# arpie_cv_tab.net
KiCad netlist of a schematic drawn in EAGLE
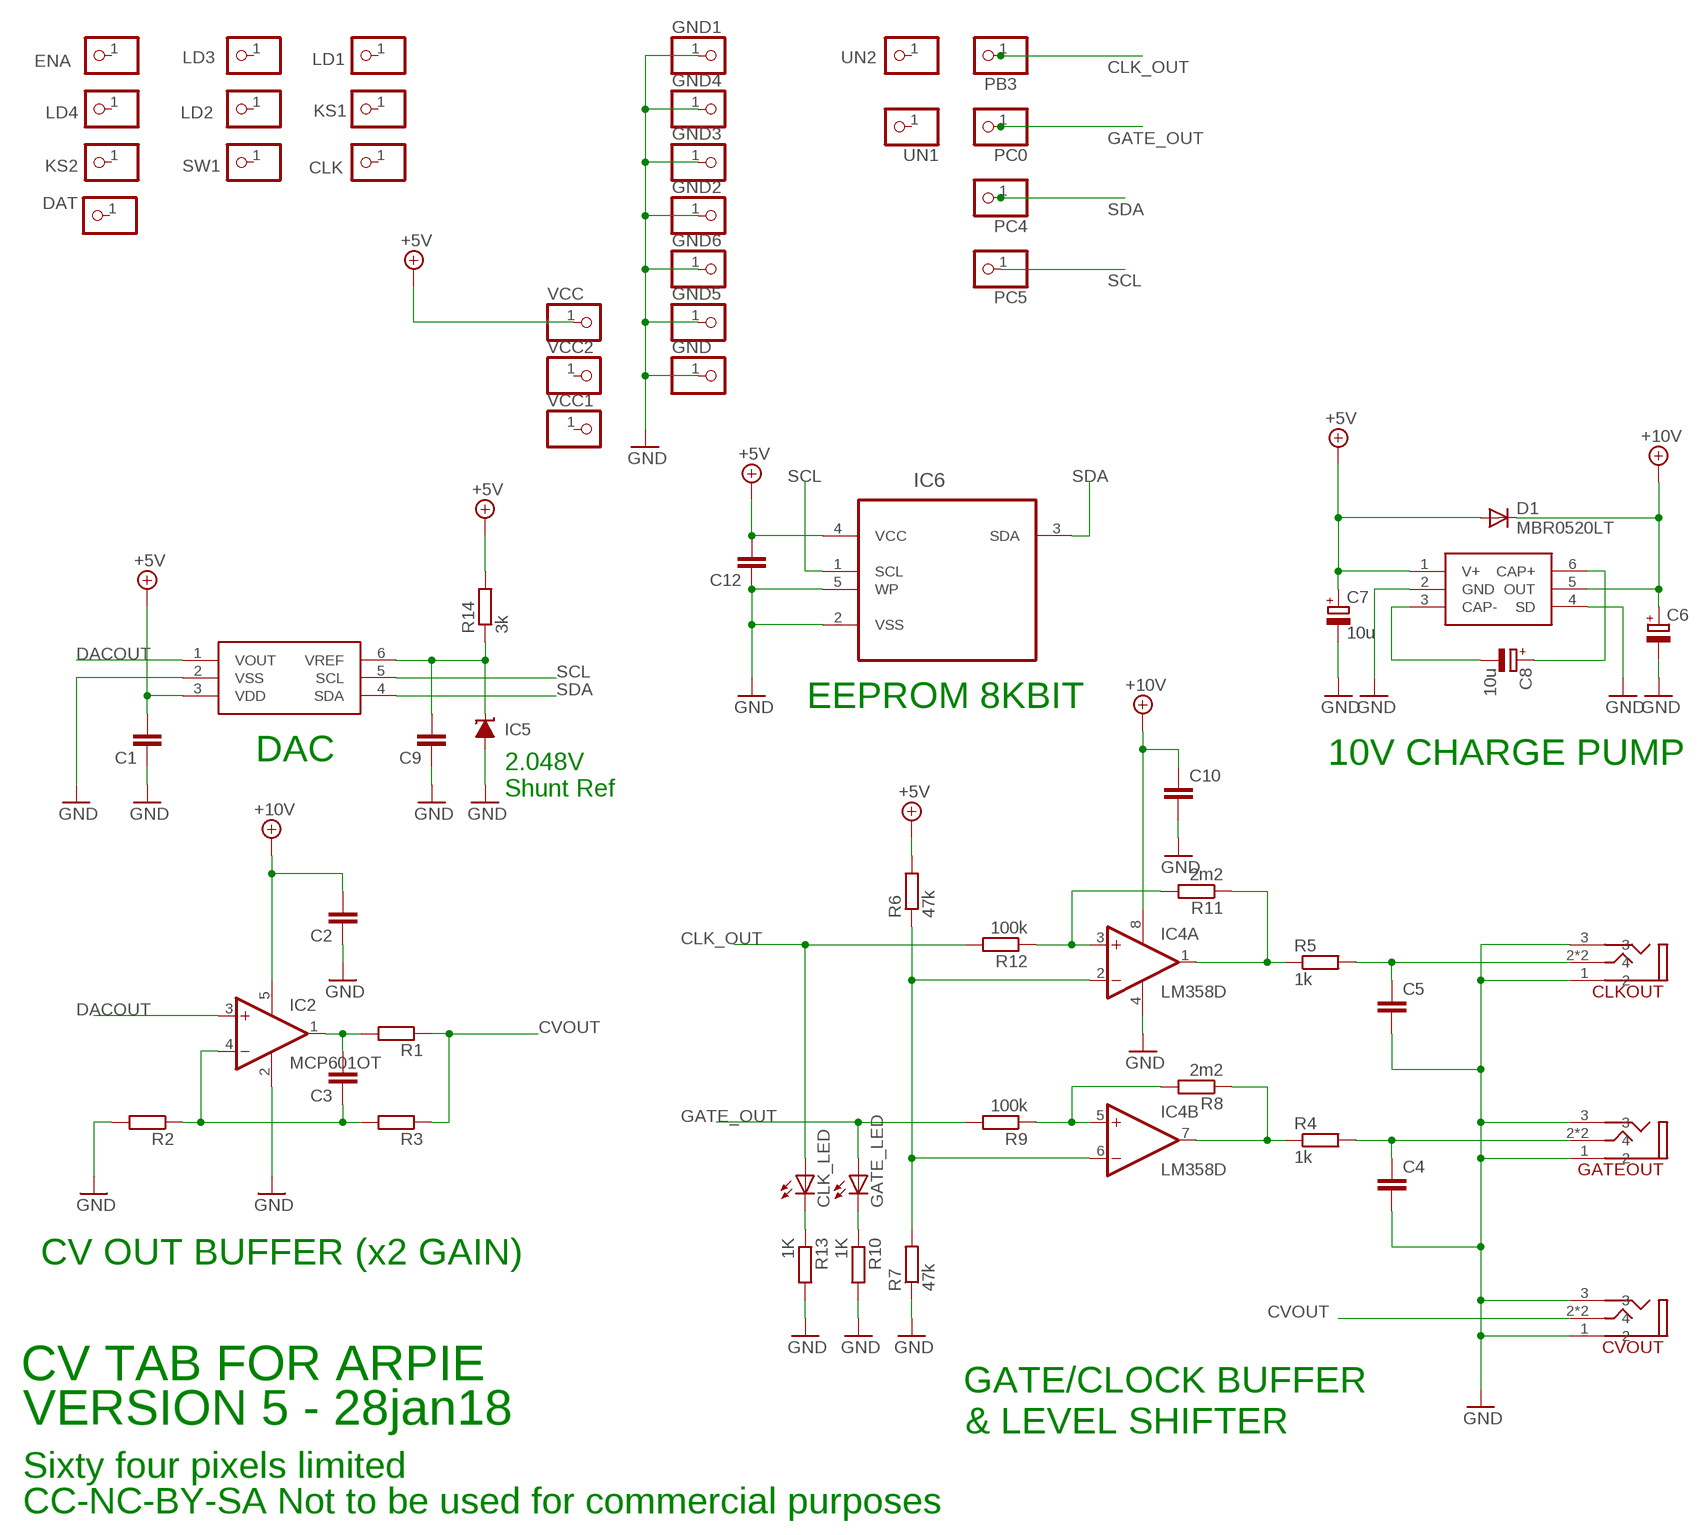
[diagram p0: schematic, sheet 1]

(export (version "E")
  (design (tool "Eeschema 10.0.6"))
  (components
    (comp (ref "C1")
      (value "C-EUC0805")
      (footprint "eagle-import:C0805")
      (libsource (lib "eagle-import") (part "C-EUC0805"))
    )
    (comp (ref "C2")
      (value "C-EUC0805")
      (footprint "eagle-import:C0805")
      (libsource (lib "eagle-import") (part "C-EUC0805"))
    )
    (comp (ref "C3")
      (value "C-EUC0805")
      (footprint "eagle-import:C0805")
      (libsource (lib "eagle-import") (part "C-EUC0805"))
    )
    (comp (ref "C4")
      (value "C-EUC0805")
      (footprint "eagle-import:C0805")
      (libsource (lib "eagle-import") (part "C-EUC0805"))
    )
    (comp (ref "C5")
      (value "C-EUC0805")
      (footprint "eagle-import:C0805")
      (libsource (lib "eagle-import") (part "C-EUC0805"))
    )
    (comp (ref "C6")
      (value "CPOL-EUSMCA")
      (footprint "eagle-import:SMC_A")
      (libsource (lib "eagle-import") (part "CPOL-EUSMCA"))
    )
    (comp (ref "C7")
      (value "10u")
      (footprint "eagle-import:SMC_A")
      (libsource (lib "eagle-import") (part "CPOL-EUSMCA"))
    )
    (comp (ref "C8")
      (value "10u")
      (footprint "eagle-import:SMC_A")
      (libsource (lib "eagle-import") (part "CPOL-EUSMCA"))
    )
    (comp (ref "C9")
      (value "C-EUC0805")
      (footprint "eagle-import:C0805")
      (libsource (lib "eagle-import") (part "C-EUC0805"))
    )
    (comp (ref "C10")
      (value "C-EUC0805")
      (footprint "eagle-import:C0805")
      (libsource (lib "eagle-import") (part "C-EUC0805"))
    )
    (comp (ref "C12")
      (value "C-EUC0805")
      (footprint "eagle-import:C0805")
      (libsource (lib "eagle-import") (part "C-EUC0805"))
    )
    (comp (ref "CLK")
      (value "PINHD-1X1")
      (footprint "eagle-import:1X01")
      (libsource (lib "eagle-import") (part "PINHD-1X1"))
    )
    (comp (ref "CLKOUT")
      (value "3_5MM_PTH_MICRO")
      (footprint "eagle-import:3_5MM_PTH_MICRO")
      (libsource (lib "eagle-import") (part "3_5MM_PTH_MICRO"))
    )
    (comp (ref "CLK_LED")
      (value "LEDCHIP-LED0805")
      (footprint "eagle-import:CHIP-LED0805")
      (libsource (lib "eagle-import") (part "LEDCHIP-LED0805"))
    )
    (comp (ref "CVOUT")
      (value "3_5MM_PTH_MICRO")
      (footprint "eagle-import:3_5MM_PTH_MICRO")
      (libsource (lib "eagle-import") (part "3_5MM_PTH_MICRO"))
    )
    (comp (ref "D1")
      (value "MBR0520LT")
      (footprint "eagle-import:SOD123")
      (libsource (lib "eagle-import") (part "MBR0520LT"))
    )
    (comp (ref "DAT")
      (value "PINHD-1X1")
      (footprint "eagle-import:1X01")
      (libsource (lib "eagle-import") (part "PINHD-1X1"))
    )
    (comp (ref "ENA")
      (value "PINHD-1X1")
      (footprint "eagle-import:1X01")
      (libsource (lib "eagle-import") (part "PINHD-1X1"))
    )
    (comp (ref "GATEOUT")
      (value "3_5MM_PTH_MICRO")
      (footprint "eagle-import:3_5MM_PTH_MICRO")
      (libsource (lib "eagle-import") (part "3_5MM_PTH_MICRO"))
    )
    (comp (ref "GATE_LED")
      (value "LEDCHIP-LED0805")
      (footprint "eagle-import:CHIP-LED0805")
      (libsource (lib "eagle-import") (part "LEDCHIP-LED0805"))
    )
    (comp (ref "GND")
      (value "PINHD-1X1")
      (footprint "eagle-import:1X01")
      (libsource (lib "eagle-import") (part "PINHD-1X1"))
    )
    (comp (ref "GND1")
      (value "PINHD-1X1")
      (footprint "eagle-import:1X01")
      (libsource (lib "eagle-import") (part "PINHD-1X1"))
    )
    (comp (ref "GND2")
      (value "PINHD-1X1")
      (footprint "eagle-import:1X01")
      (libsource (lib "eagle-import") (part "PINHD-1X1"))
    )
    (comp (ref "GND3")
      (value "PINHD-1X1")
      (footprint "eagle-import:1X01")
      (libsource (lib "eagle-import") (part "PINHD-1X1"))
    )
    (comp (ref "GND4")
      (value "PINHD-1X1")
      (footprint "eagle-import:1X01")
      (libsource (lib "eagle-import") (part "PINHD-1X1"))
    )
    (comp (ref "GND5")
      (value "PINHD-1X1")
      (footprint "eagle-import:1X01")
      (libsource (lib "eagle-import") (part "PINHD-1X1"))
    )
    (comp (ref "GND6")
      (value "PINHD-1X1")
      (footprint "eagle-import:1X01")
      (libsource (lib "eagle-import") (part "PINHD-1X1"))
    )
    (comp (ref "IC1")
      (value "MCP4726")
      (footprint "eagle-import:SOT23-6")
      (libsource (lib "eagle-import") (part "MCP4726"))
    )
    (comp (ref "IC2")
      (value "MCP601OT")
      (footprint "eagle-import:SOT23-5")
      (libsource (lib "eagle-import") (part "MCP601OT"))
    )
    (comp (ref "IC3")
      (value "LM27675M5_CHARGEPUMP")
      (footprint "eagle-import:SOT23-6")
      (libsource (lib "eagle-import") (part "LM27675M5_CHARGEPUMP"))
    )
    (comp (ref "IC4")
      (value "LM358D")
      (footprint "eagle-import:SO08")
      (libsource (lib "eagle-import") (part "LM358D"))
    )
    (comp (ref "IC5")
      (value "LM4041A12DBZ")
      (footprint "eagle-import:DBZ_R-PDSO-G3")
      (fields (field (name "MPN") "LM4041A12IDBZR"))
      (libsource (lib "eagle-import") (part "LM4041DBZA12"))
    )
    (comp (ref "IC6")
      (value "24LC_16BT-I/OT")
      (footprint "eagle-import:SOT95P290X145-5N")
      (fields (field (name "MPN") "24LC16BT-I/OT "))
      (libsource (lib "eagle-import") (part "24LC_16BT-I/OT"))
    )
    (comp (ref "KS1")
      (value "PINHD-1X1")
      (footprint "eagle-import:1X01")
      (libsource (lib "eagle-import") (part "PINHD-1X1"))
    )
    (comp (ref "KS2")
      (value "PINHD-1X1")
      (footprint "eagle-import:1X01")
      (libsource (lib "eagle-import") (part "PINHD-1X1"))
    )
    (comp (ref "LD1")
      (value "PINHD-1X1")
      (footprint "eagle-import:1X01")
      (libsource (lib "eagle-import") (part "PINHD-1X1"))
    )
    (comp (ref "LD2")
      (value "PINHD-1X1")
      (footprint "eagle-import:1X01")
      (libsource (lib "eagle-import") (part "PINHD-1X1"))
    )
    (comp (ref "LD3")
      (value "PINHD-1X1")
      (footprint "eagle-import:1X01")
      (libsource (lib "eagle-import") (part "PINHD-1X1"))
    )
    (comp (ref "LD4")
      (value "PINHD-1X1")
      (footprint "eagle-import:1X01")
      (libsource (lib "eagle-import") (part "PINHD-1X1"))
    )
    (comp (ref "PB3")
      (value "PINHD-1X1")
      (footprint "eagle-import:1X01")
      (libsource (lib "eagle-import") (part "PINHD-1X1"))
    )
    (comp (ref "PC0")
      (value "PINHD-1X1")
      (footprint "eagle-import:1X01")
      (libsource (lib "eagle-import") (part "PINHD-1X1"))
    )
    (comp (ref "PC4")
      (value "PINHD-1X1")
      (footprint "eagle-import:1X01")
      (libsource (lib "eagle-import") (part "PINHD-1X1"))
    )
    (comp (ref "PC5")
      (value "PINHD-1X1")
      (footprint "eagle-import:1X01")
      (libsource (lib "eagle-import") (part "PINHD-1X1"))
    )
    (comp (ref "R1")
      (value "R-EU_R0805")
      (footprint "eagle-import:R0805")
      (libsource (lib "eagle-import") (part "R-EU_R0805"))
    )
    (comp (ref "R2")
      (value "R-EU_R0805")
      (footprint "eagle-import:R0805")
      (libsource (lib "eagle-import") (part "R-EU_R0805"))
    )
    (comp (ref "R3")
      (value "R-EU_R0805")
      (footprint "eagle-import:R0805")
      (libsource (lib "eagle-import") (part "R-EU_R0805"))
    )
    (comp (ref "R4")
      (value "1k")
      (footprint "eagle-import:R0805")
      (libsource (lib "eagle-import") (part "R-EU_R0805"))
    )
    (comp (ref "R5")
      (value "1k")
      (footprint "eagle-import:R0805")
      (libsource (lib "eagle-import") (part "R-EU_R0805"))
    )
    (comp (ref "R6")
      (value "47k")
      (footprint "eagle-import:R0805")
      (libsource (lib "eagle-import") (part "R-EU_R0805"))
    )
    (comp (ref "R7")
      (value "47k")
      (footprint "eagle-import:R0805")
      (libsource (lib "eagle-import") (part "R-EU_R0805"))
    )
    (comp (ref "R8")
      (value "2m2")
      (footprint "eagle-import:R0805")
      (libsource (lib "eagle-import") (part "R-EU_R0805"))
    )
    (comp (ref "R9")
      (value "100k")
      (footprint "eagle-import:R0805")
      (libsource (lib "eagle-import") (part "R-EU_R0805"))
    )
    (comp (ref "R10")
      (value "1K")
      (footprint "eagle-import:R0805")
      (libsource (lib "eagle-import") (part "R-EU_R0805"))
    )
    (comp (ref "R11")
      (value "2m2")
      (footprint "eagle-import:R0805")
      (libsource (lib "eagle-import") (part "R-EU_R0805"))
    )
    (comp (ref "R12")
      (value "100k")
      (footprint "eagle-import:R0805")
      (libsource (lib "eagle-import") (part "R-EU_R0805"))
    )
    (comp (ref "R13")
      (value "1K")
      (footprint "eagle-import:R0805")
      (libsource (lib "eagle-import") (part "R-EU_R0805"))
    )
    (comp (ref "R14")
      (value "3k")
      (footprint "eagle-import:R0805")
      (libsource (lib "eagle-import") (part "R-EU_R0805"))
    )
    (comp (ref "SW1")
      (value "PINHD-1X1")
      (footprint "eagle-import:1X01")
      (libsource (lib "eagle-import") (part "PINHD-1X1"))
    )
    (comp (ref "UN1")
      (value "PINHD-1X1")
      (footprint "eagle-import:1X01")
      (libsource (lib "eagle-import") (part "PINHD-1X1"))
    )
    (comp (ref "UN2")
      (value "PINHD-1X1")
      (footprint "eagle-import:1X01")
      (libsource (lib "eagle-import") (part "PINHD-1X1"))
    )
    (comp (ref "VCC")
      (value "PINHD-1X1")
      (footprint "eagle-import:1X01")
      (libsource (lib "eagle-import") (part "PINHD-1X1"))
    )
    (comp (ref "VCC1")
      (value "PINHD-1X1")
      (footprint "eagle-import:1X01")
      (libsource (lib "eagle-import") (part "PINHD-1X1"))
    )
    (comp (ref "VCC2")
      (value "PINHD-1X1")
      (footprint "eagle-import:1X01")
      (libsource (lib "eagle-import") (part "PINHD-1X1"))
    )
  )
  (nets
    (net (code "1") (name "+5V") (class "Default")
      (node (ref "C1") (pin "2") (pinfunction "2_2") (pintype "passive"))
      (node (ref "C12") (pin "2") (pinfunction "2_2") (pintype "passive"))
      (node (ref "C7") (pin "+") (pinfunction "+_+") (pintype "passive"))
      (node (ref "D1") (pin "A") (pinfunction "A_A") (pintype "passive"))
      (node (ref "IC1") (pin "3") (pinfunction "VDD_3") (pintype "power_in"))
      (node (ref "IC3") (pin "1") (pinfunction "V+_1") (pintype "bidirectional"))
      (node (ref "IC6") (pin "4") (pinfunction "VCC_4") (pintype "power_in"))
      (node (ref "R14") (pin "2") (pinfunction "2_2") (pintype "passive"))
      (node (ref "R6") (pin "2") (pinfunction "2_2") (pintype "passive"))
      (node (ref "VCC") (pin "1") (pinfunction "1_1") (pintype "passive"))
    )
    (net (code "2") (name "+10V") (class "Default")
      (node (ref "C10") (pin "1") (pinfunction "1_1") (pintype "passive"))
      (node (ref "C2") (pin "2") (pinfunction "2_2") (pintype "passive"))
      (node (ref "C6") (pin "+") (pinfunction "+_+") (pintype "passive"))
      (node (ref "D1") (pin "C") (pinfunction "C_C") (pintype "passive"))
      (node (ref "IC2") (pin "5") (pinfunction "V+_5") (pintype "power_in"))
      (node (ref "IC3") (pin "5") (pinfunction "OUT_5") (pintype "bidirectional"))
      (node (ref "IC4") (pin "8") (pinfunction "V+_8") (pintype "power_in"))
    )
    (net (code "3") (name "/CLK_OUT") (class "Default")
      (node (ref "CLK_LED") (pin "A") (pinfunction "A_A") (pintype "passive"))
      (node (ref "PB3") (pin "1") (pinfunction "1_1") (pintype "passive"))
      (node (ref "R12") (pin "2") (pinfunction "2_2") (pintype "passive"))
    )
    (net (code "4") (name "/CVOUT") (class "Default")
      (node (ref "CVOUT") (pin "2") (pinfunction "4_2") (pintype "bidirectional"))
      (node (ref "CVOUT") (pin "2A") (pinfunction "4_2A") (pintype "bidirectional"))
      (node (ref "R1") (pin "1") (pinfunction "1_1") (pintype "passive"))
      (node (ref "R3") (pin "1") (pinfunction "1_1") (pintype "passive"))
    )
    (net (code "5") (name "/DACOUT") (class "Default")
      (node (ref "IC1") (pin "1") (pinfunction "VOUT_1") (pintype "output"))
      (node (ref "IC2") (pin "3") (pinfunction "+IN_3") (pintype "input"))
    )
    (net (code "6") (name "/GATE_OUT") (class "Default")
      (node (ref "GATE_LED") (pin "A") (pinfunction "A_A") (pintype "passive"))
      (node (ref "PC0") (pin "1") (pinfunction "1_1") (pintype "passive"))
      (node (ref "R9") (pin "2") (pinfunction "2_2") (pintype "passive"))
    )
    (net (code "7") (name "/SCL") (class "Default")
      (node (ref "IC1") (pin "5") (pinfunction "SCL_5") (pintype "bidirectional"))
      (node (ref "IC6") (pin "1") (pinfunction "SCL_1") (pintype "input"))
      (node (ref "PC5") (pin "1") (pinfunction "1_1") (pintype "passive"))
    )
    (net (code "8") (name "/SDA") (class "Default")
      (node (ref "IC1") (pin "4") (pinfunction "SDA_4") (pintype "bidirectional"))
      (node (ref "IC6") (pin "3") (pinfunction "SDA_3") (pintype "bidirectional"))
      (node (ref "PC4") (pin "1") (pinfunction "1_1") (pintype "passive"))
    )
    (net (code "9") (name "GND") (class "Default")
      (node (ref "C1") (pin "1") (pinfunction "1_1") (pintype "passive"))
      (node (ref "C10") (pin "2") (pinfunction "2_2") (pintype "passive"))
      (node (ref "C12") (pin "1") (pinfunction "1_1") (pintype "passive"))
      (node (ref "C2") (pin "1") (pinfunction "1_1") (pintype "passive"))
      (node (ref "C4") (pin "2") (pinfunction "2_2") (pintype "passive"))
      (node (ref "C5") (pin "2") (pinfunction "2_2") (pintype "passive"))
      (node (ref "C6") (pin "-") (pinfunction "-_-") (pintype "passive"))
      (node (ref "C7") (pin "-") (pinfunction "-_-") (pintype "passive"))
      (node (ref "C9") (pin "1") (pinfunction "1_1") (pintype "passive"))
      (node (ref "CLKOUT") (pin "1") (pinfunction "2_1") (pintype "bidirectional"))
      (node (ref "CLKOUT") (pin "3") (pinfunction "3_3") (pintype "bidirectional"))
      (node (ref "CVOUT") (pin "1") (pinfunction "2_1") (pintype "bidirectional"))
      (node (ref "CVOUT") (pin "3") (pinfunction "3_3") (pintype "bidirectional"))
      (node (ref "GATEOUT") (pin "1") (pinfunction "2_1") (pintype "bidirectional"))
      (node (ref "GATEOUT") (pin "3") (pinfunction "3_3") (pintype "bidirectional"))
      (node (ref "GND") (pin "1") (pinfunction "1_1") (pintype "passive"))
      (node (ref "GND1") (pin "1") (pinfunction "1_1") (pintype "passive"))
      (node (ref "GND2") (pin "1") (pinfunction "1_1") (pintype "passive"))
      (node (ref "GND3") (pin "1") (pinfunction "1_1") (pintype "passive"))
      (node (ref "GND4") (pin "1") (pinfunction "1_1") (pintype "passive"))
      (node (ref "GND5") (pin "1") (pinfunction "1_1") (pintype "passive"))
      (node (ref "GND6") (pin "1") (pinfunction "1_1") (pintype "passive"))
      (node (ref "IC1") (pin "2") (pinfunction "VSS_2") (pintype "power_in"))
      (node (ref "IC2") (pin "2") (pinfunction "V-_2") (pintype "power_in"))
      (node (ref "IC3") (pin "2") (pinfunction "GND_2") (pintype "bidirectional"))
      (node (ref "IC3") (pin "4") (pinfunction "SD_4") (pintype "bidirectional"))
      (node (ref "IC4") (pin "4") (pinfunction "V-_4") (pintype "power_in"))
      (node (ref "IC5") (pin "2") (pinfunction "A_2") (pintype "passive"))
      (node (ref "IC6") (pin "2") (pinfunction "VSS_2") (pintype "passive"))
      (node (ref "IC6") (pin "5") (pinfunction "WP_5") (pintype "input"))
      (node (ref "R10") (pin "2") (pinfunction "2_2") (pintype "passive"))
      (node (ref "R13") (pin "2") (pinfunction "2_2") (pintype "passive"))
      (node (ref "R2") (pin "2") (pinfunction "2_2") (pintype "passive"))
      (node (ref "R7") (pin "1") (pinfunction "1_1") (pintype "passive"))
    )
    (net (code "10") (name "Net-(C4-Pad1)") (class "Default")
      (node (ref "C4") (pin "1") (pinfunction "1_1") (pintype "passive"))
      (node (ref "GATEOUT") (pin "2") (pinfunction "4_2") (pintype "bidirectional"))
      (node (ref "GATEOUT") (pin "2A") (pinfunction "4_2A") (pintype "bidirectional"))
      (node (ref "R4") (pin "2") (pinfunction "2_2") (pintype "passive"))
    )
    (net (code "11") (name "Net-(C5-Pad1)") (class "Default")
      (node (ref "C5") (pin "1") (pinfunction "1_1") (pintype "passive"))
      (node (ref "CLKOUT") (pin "2") (pinfunction "4_2") (pintype "bidirectional"))
      (node (ref "CLKOUT") (pin "2A") (pinfunction "4_2A") (pintype "bidirectional"))
      (node (ref "R5") (pin "2") (pinfunction "2_2") (pintype "passive"))
    )
    (net (code "12") (name "Net-(CLK_LED-PadC)") (class "Default")
      (node (ref "CLK_LED") (pin "C") (pinfunction "C_C") (pintype "passive"))
      (node (ref "R13") (pin "1") (pinfunction "1_1") (pintype "passive"))
    )
    (net (code "13") (name "Net-(GATE_LED-PadC)") (class "Default")
      (node (ref "GATE_LED") (pin "C") (pinfunction "C_C") (pintype "passive"))
      (node (ref "R10") (pin "1") (pinfunction "1_1") (pintype "passive"))
    )
    (net (code "14") (name "Net-(IC1-VREF)") (class "Default")
      (node (ref "C9") (pin "2") (pinfunction "2_2") (pintype "passive"))
      (node (ref "IC1") (pin "6") (pinfunction "VREF_6") (pintype "input"))
      (node (ref "IC5") (pin "1") (pinfunction "C_1") (pintype "passive"))
      (node (ref "R14") (pin "1") (pinfunction "1_1") (pintype "passive"))
    )
    (net (code "15") (name "Net-(IC2--IN)") (class "Default")
      (node (ref "C3") (pin "1") (pinfunction "1_1") (pintype "passive"))
      (node (ref "IC2") (pin "4") (pinfunction "-IN_4") (pintype "input"))
      (node (ref "R2") (pin "1") (pinfunction "1_1") (pintype "passive"))
      (node (ref "R3") (pin "2") (pinfunction "2_2") (pintype "passive"))
    )
    (net (code "16") (name "Net-(IC2-OUT)") (class "Default")
      (node (ref "C3") (pin "2") (pinfunction "2_2") (pintype "passive"))
      (node (ref "IC2") (pin "1") (pinfunction "OUT_1") (pintype "output"))
      (node (ref "R1") (pin "2") (pinfunction "2_2") (pintype "passive"))
    )
    (net (code "17") (name "Net-(IC3-CAP+)") (class "Default")
      (node (ref "C8") (pin "+") (pinfunction "+_+") (pintype "passive"))
      (node (ref "IC3") (pin "6") (pinfunction "CAP+_6") (pintype "bidirectional"))
    )
    (net (code "18") (name "Net-(IC3-CAP-)") (class "Default")
      (node (ref "C8") (pin "-") (pinfunction "-_-") (pintype "passive"))
      (node (ref "IC3") (pin "3") (pinfunction "CAP-_3") (pintype "bidirectional"))
    )
    (net (code "19") (name "Net-(IC4A-+IN)") (class "Default")
      (node (ref "IC4") (pin "3") (pinfunction "+IN_3") (pintype "input"))
      (node (ref "R11") (pin "2") (pinfunction "2_2") (pintype "passive"))
      (node (ref "R12") (pin "1") (pinfunction "1_1") (pintype "passive"))
    )
    (net (code "20") (name "Net-(IC4A--IN)") (class "Default")
      (node (ref "IC4") (pin "2") (pinfunction "-IN_2") (pintype "input"))
      (node (ref "IC4") (pin "6") (pinfunction "-IN_6") (pintype "input"))
      (node (ref "R6") (pin "1") (pinfunction "1_1") (pintype "passive"))
      (node (ref "R7") (pin "2") (pinfunction "2_2") (pintype "passive"))
    )
    (net (code "21") (name "Net-(IC4A-OUT)") (class "Default")
      (node (ref "IC4") (pin "1") (pinfunction "OUT_1") (pintype "output"))
      (node (ref "R11") (pin "1") (pinfunction "1_1") (pintype "passive"))
      (node (ref "R5") (pin "1") (pinfunction "1_1") (pintype "passive"))
    )
    (net (code "22") (name "Net-(IC4B-+IN)") (class "Default")
      (node (ref "IC4") (pin "5") (pinfunction "+IN_5") (pintype "input"))
      (node (ref "R8") (pin "2") (pinfunction "2_2") (pintype "passive"))
      (node (ref "R9") (pin "1") (pinfunction "1_1") (pintype "passive"))
    )
    (net (code "23") (name "Net-(IC4B-OUT)") (class "Default")
      (node (ref "IC4") (pin "7") (pinfunction "OUT_7") (pintype "output"))
      (node (ref "R4") (pin "1") (pinfunction "1_1") (pintype "passive"))
      (node (ref "R8") (pin "1") (pinfunction "1_1") (pintype "passive"))
    )
    (net (code "24") (name "unconnected-(CLK-Pad1)") (class "Default")
      (node (ref "CLK") (pin "1") (pinfunction "1_1") (pintype "passive"))
    )
    (net (code "25") (name "unconnected-(DAT-Pad1)") (class "Default")
      (node (ref "DAT") (pin "1") (pinfunction "1_1") (pintype "passive"))
    )
    (net (code "26") (name "unconnected-(ENA-Pad1)") (class "Default")
      (node (ref "ENA") (pin "1") (pinfunction "1_1") (pintype "passive"))
    )
    (net (code "27") (name "unconnected-(KS1-Pad1)") (class "Default")
      (node (ref "KS1") (pin "1") (pinfunction "1_1") (pintype "passive"))
    )
    (net (code "28") (name "unconnected-(KS2-Pad1)") (class "Default")
      (node (ref "KS2") (pin "1") (pinfunction "1_1") (pintype "passive"))
    )
    (net (code "29") (name "unconnected-(LD1-Pad1)") (class "Default")
      (node (ref "LD1") (pin "1") (pinfunction "1_1") (pintype "passive"))
    )
    (net (code "30") (name "unconnected-(LD2-Pad1)") (class "Default")
      (node (ref "LD2") (pin "1") (pinfunction "1_1") (pintype "passive"))
    )
    (net (code "31") (name "unconnected-(LD3-Pad1)") (class "Default")
      (node (ref "LD3") (pin "1") (pinfunction "1_1") (pintype "passive"))
    )
    (net (code "32") (name "unconnected-(LD4-Pad1)") (class "Default")
      (node (ref "LD4") (pin "1") (pinfunction "1_1") (pintype "passive"))
    )
    (net (code "33") (name "unconnected-(SW1-Pad1)") (class "Default")
      (node (ref "SW1") (pin "1") (pinfunction "1_1") (pintype "passive"))
    )
    (net (code "34") (name "unconnected-(UN1-Pad1)") (class "Default")
      (node (ref "UN1") (pin "1") (pinfunction "1_1") (pintype "passive"))
    )
    (net (code "35") (name "unconnected-(UN2-Pad1)") (class "Default")
      (node (ref "UN2") (pin "1") (pinfunction "1_1") (pintype "passive"))
    )
    (net (code "36") (name "unconnected-(VCC1-Pad1)") (class "Default")
      (node (ref "VCC1") (pin "1") (pinfunction "1_1") (pintype "passive"))
    )
    (net (code "37") (name "unconnected-(VCC2-Pad1)") (class "Default")
      (node (ref "VCC2") (pin "1") (pinfunction "1_1") (pintype "passive"))
    )
  )
)
